# GTY_Transceivers.net
KiCad netlist of a schematic drawn in Altium Designer
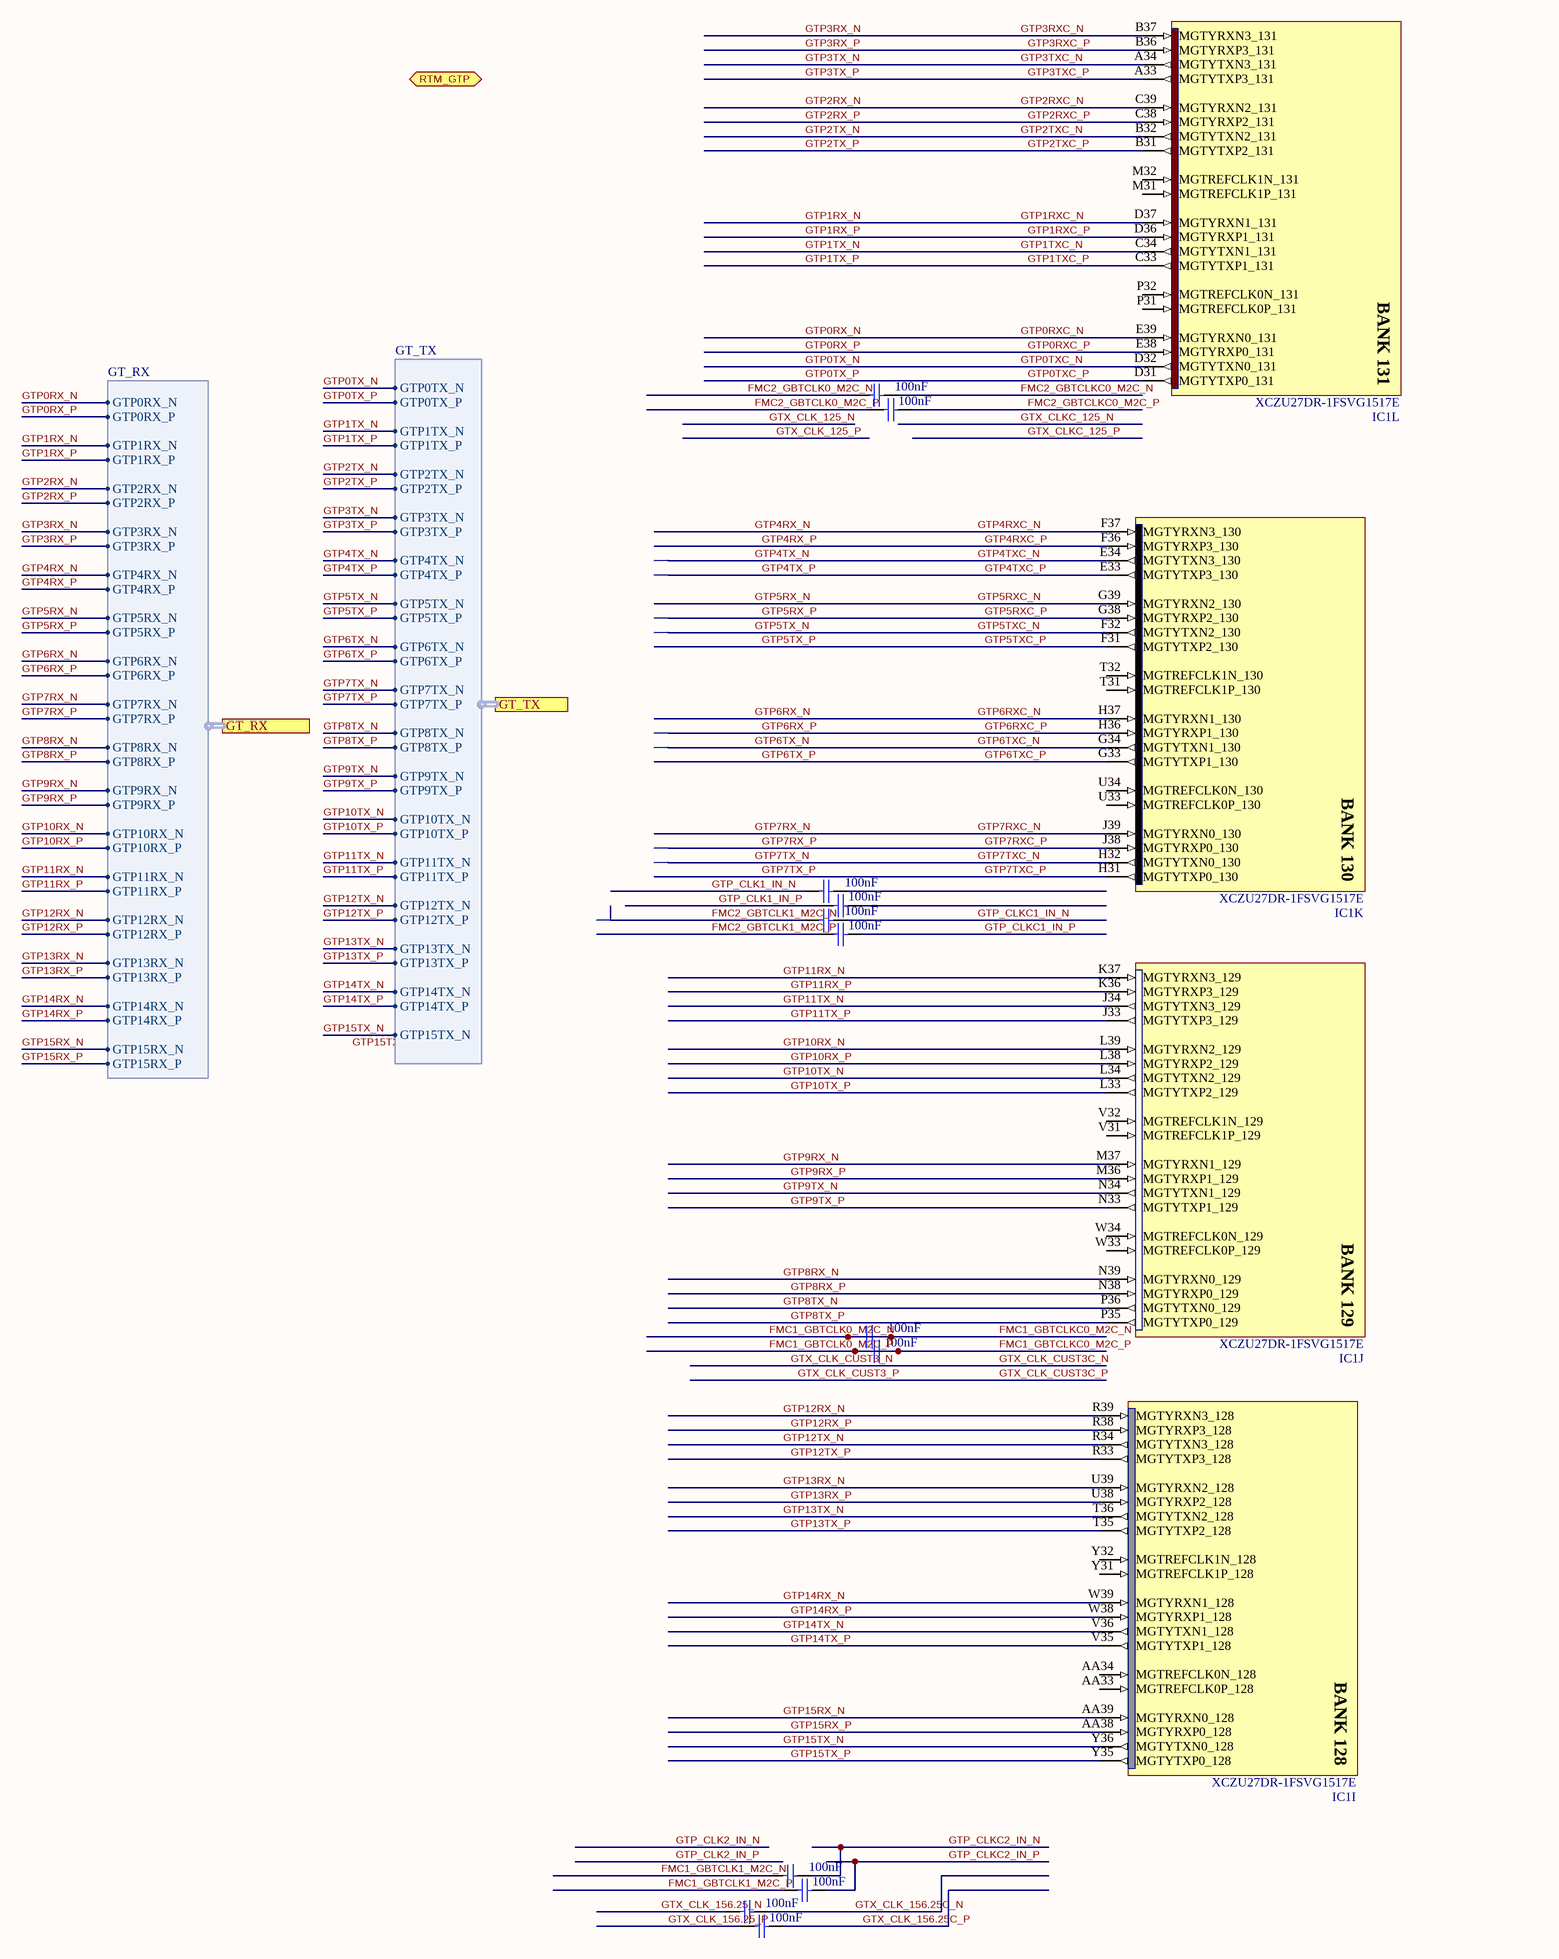
[diagram p0: GTY_Transceivers.SchDoc]

(export (version "E")
  (design (tool "Eeschema 10.0.6"))
  (components
    (comp (ref "C435")
      (value "100nF")
      (fields
        (field (name "$$NOTCOMMONPROPERTY_GENERAL PART NUMBER") "CC0201_100NF_6.3V_10%_X5R")
        (field (name "$$NOTCOMMONPROPERTY_MANUFACTURER1 PART NUMBER") "02016D104KAT2A")
        (field (name "MANUFACTURER") "GENERIC")
      )
      (libsource (lib "altium-import") (part "root_0__*"))
    )
    (comp (ref "C436")
      (value "100nF")
      (fields
        (field (name "$$NOTCOMMONPROPERTY_GENERAL PART NUMBER") "CC0201_100NF_6.3V_10%_X5R")
        (field (name "$$NOTCOMMONPROPERTY_MANUFACTURER1 PART NUMBER") "02016D104KAT2A")
        (field (name "MANUFACTURER") "GENERIC")
      )
      (libsource (lib "altium-import") (part "root_0__*"))
    )
    (comp (ref "C595")
      (value "100nF")
      (fields
        (field (name "$$NOTCOMMONPROPERTY_GENERAL PART NUMBER") "CC0201_100NF_6.3V_10%_X5R")
        (field (name "$$NOTCOMMONPROPERTY_MANUFACTURER1 PART NUMBER") "02016D104KAT2A")
        (field (name "MANUFACTURER") "GENERIC")
      )
      (libsource (lib "altium-import") (part "root_0__*"))
    )
    (comp (ref "C596")
      (value "100nF")
      (fields
        (field (name "$$NOTCOMMONPROPERTY_GENERAL PART NUMBER") "CC0201_100NF_6.3V_10%_X5R")
        (field (name "$$NOTCOMMONPROPERTY_MANUFACTURER1 PART NUMBER") "02016D104KAT2A")
        (field (name "MANUFACTURER") "GENERIC")
      )
      (libsource (lib "altium-import") (part "root_0__*"))
    )
    (comp (ref "C623")
      (value "100nF")
      (fields
        (field (name "$$NOTCOMMONPROPERTY_GENERAL PART NUMBER") "CC0201_100NF_6.3V_10%_X5R")
        (field (name "$$NOTCOMMONPROPERTY_MANUFACTURER1 PART NUMBER") "02016D104KAT2A")
        (field (name "MANUFACTURER") "GENERIC")
      )
      (libsource (lib "altium-import") (part "root_0__*"))
    )
    (comp (ref "C624")
      (value "100nF")
      (fields
        (field (name "$$NOTCOMMONPROPERTY_GENERAL PART NUMBER") "CC0201_100NF_6.3V_10%_X5R")
        (field (name "$$NOTCOMMONPROPERTY_MANUFACTURER1 PART NUMBER") "02016D104KAT2A")
        (field (name "MANUFACTURER") "GENERIC")
      )
      (libsource (lib "altium-import") (part "root_0__*"))
    )
    (comp (ref "C625")
      (value "100nF")
      (fields
        (field (name "$$NOTCOMMONPROPERTY_GENERAL PART NUMBER") "CC0201_100NF_6.3V_10%_X5R")
        (field (name "$$NOTCOMMONPROPERTY_MANUFACTURER1 PART NUMBER") "02016D104KAT2A")
        (field (name "MANUFACTURER") "GENERIC")
      )
      (libsource (lib "altium-import") (part "root_0__*"))
    )
    (comp (ref "C626")
      (value "100nF")
      (fields
        (field (name "$$NOTCOMMONPROPERTY_GENERAL PART NUMBER") "CC0201_100NF_6.3V_10%_X5R")
        (field (name "$$NOTCOMMONPROPERTY_MANUFACTURER1 PART NUMBER") "02016D104KAT2A")
        (field (name "MANUFACTURER") "GENERIC")
      )
      (libsource (lib "altium-import") (part "root_0__*"))
    )
    (comp (ref "C643")
      (value "100nF")
      (fields
        (field (name "$$NOTCOMMONPROPERTY_GENERAL PART NUMBER") "CC0201_100NF_6.3V_10%_X5R")
        (field (name "$$NOTCOMMONPROPERTY_MANUFACTURER1 PART NUMBER") "02016D104KAT2A")
        (field (name "MANUFACTURER") "GENERIC")
      )
      (libsource (lib "altium-import") (part "root_0__*"))
    )
    (comp (ref "C644")
      (value "100nF")
      (fields
        (field (name "$$NOTCOMMONPROPERTY_GENERAL PART NUMBER") "CC0201_100NF_6.3V_10%_X5R")
        (field (name "$$NOTCOMMONPROPERTY_MANUFACTURER1 PART NUMBER") "02016D104KAT2A")
        (field (name "MANUFACTURER") "GENERIC")
      )
      (libsource (lib "altium-import") (part "root_0__*"))
    )
    (comp (ref "C665")
      (value "100nF")
      (fields
        (field (name "$$NOTCOMMONPROPERTY_GENERAL PART NUMBER") "CC0201_100NF_6.3V_10%_X5R")
        (field (name "$$NOTCOMMONPROPERTY_MANUFACTURER1 PART NUMBER") "02016D104KAT2A")
        (field (name "MANUFACTURER") "GENERIC")
      )
      (libsource (lib "altium-import") (part "root_0__*"))
    )
    (comp (ref "C666")
      (value "100nF")
      (fields
        (field (name "$$NOTCOMMONPROPERTY_GENERAL PART NUMBER") "CC0201_100NF_6.3V_10%_X5R")
        (field (name "$$NOTCOMMONPROPERTY_MANUFACTURER1 PART NUMBER") "02016D104KAT2A")
        (field (name "MANUFACTURER") "GENERIC")
      )
      (libsource (lib "altium-import") (part "root_0__*"))
    )
    (comp (ref "IC1")
      (value "XCZU27DR-1FSVG1517E")
      (footprint "XILINX_FSVG1517 (XCZU27DR)")
      (fields (field (name "MANUFACTURER") "XILINX") (field (name "AUTHOR") "CERN DEM MR"))
      (libsource (lib "ICs And Semiconductors") (part "XCZU27DR-1FSVG1517E"))
    )
  )
  (nets
    (net (code "3") (name "/FMC1_GBTCLK0_M2C_N") (class "Default")
      (node (ref "C643") (pin "1") (pinfunction "1_1") (pintype "passive"))
      (node (ref "C643") (pin "2") (pinfunction "2_2") (pintype "passive"))
    )
    (net (code "4") (name "/FMC1_GBTCLK0_M2C_P") (class "Default")
      (node (ref "C644") (pin "1") (pinfunction "1_1") (pintype "passive"))
      (node (ref "C644") (pin "2") (pinfunction "2_2") (pintype "passive"))
    )
    (net (code "5") (name "/FMC1_GBTCLK1_M2C_N") (class "Default")
      (node (ref "C665") (pin "1") (pinfunction "1_1") (pintype "passive"))
    )
    (net (code "6") (name "/FMC1_GBTCLK1_M2C_P") (class "Default")
      (node (ref "C666") (pin "1") (pinfunction "1_1") (pintype "passive"))
    )
    (net (code "7") (name "/FMC2_GBTCLK0_M2C_N") (class "Default")
      (node (ref "C595") (pin "1") (pinfunction "1_1") (pintype "passive"))
    )
    (net (code "8") (name "/FMC2_GBTCLK0_M2C_P") (class "Default")
      (node (ref "C596") (pin "1") (pinfunction "1_1") (pintype "passive"))
    )
    (net (code "9") (name "/FMC2_GBTCLK1_M2C_N") (class "Default")
      (node (ref "C625") (pin "1") (pinfunction "1_1") (pintype "passive"))
    )
    (net (code "10") (name "/FMC2_GBTCLK1_M2C_P") (class "Default")
      (node (ref "C626") (pin "1") (pinfunction "1_1") (pintype "passive"))
    )
    (net (code "11") (name "/FMC2_GBTCLKC0_M2C_N") (class "Default")
      (node (ref "C595") (pin "2") (pinfunction "2_2") (pintype "passive"))
    )
    (net (code "12") (name "/FMC2_GBTCLKC0_M2C_P") (class "Default")
      (node (ref "C596") (pin "2") (pinfunction "2_2") (pintype "passive"))
    )
    (net (code "13") (name "/GTP0RXC_N") (class "Default")
      (node (ref "IC1") (pin "E39") (pinfunction "MGTYRXN0_131_E39") (pintype "input"))
    )
    (net (code "14") (name "/GTP0RXC_P") (class "Default")
      (node (ref "IC1") (pin "E38") (pinfunction "MGTYRXP0_131_E38") (pintype "input"))
    )
    (net (code "15") (name "/GTP0TXC_N") (class "Default")
      (node (ref "IC1") (pin "D32") (pinfunction "MGTYTXN0_131_D32") (pintype "output"))
    )
    (net (code "16") (name "/GTP0TXC_P") (class "Default")
      (node (ref "IC1") (pin "D31") (pinfunction "MGTYTXP0_131_D31") (pintype "output"))
    )
    (net (code "17") (name "/GTP1RXC_N") (class "Default")
      (node (ref "IC1") (pin "D37") (pinfunction "MGTYRXN1_131_D37") (pintype "input"))
    )
    (net (code "18") (name "/GTP1RXC_P") (class "Default")
      (node (ref "IC1") (pin "D36") (pinfunction "MGTYRXP1_131_D36") (pintype "input"))
    )
    (net (code "19") (name "/GTP1TXC_N") (class "Default")
      (node (ref "IC1") (pin "C34") (pinfunction "MGTYTXN1_131_C34") (pintype "output"))
    )
    (net (code "20") (name "/GTP1TXC_P") (class "Default")
      (node (ref "IC1") (pin "C33") (pinfunction "MGTYTXP1_131_C33") (pintype "output"))
    )
    (net (code "21") (name "/GTP2RXC_N") (class "Default")
      (node (ref "IC1") (pin "C39") (pinfunction "MGTYRXN2_131_C39") (pintype "input"))
    )
    (net (code "22") (name "/GTP2RXC_P") (class "Default")
      (node (ref "IC1") (pin "C38") (pinfunction "MGTYRXP2_131_C38") (pintype "input"))
    )
    (net (code "23") (name "/GTP2TXC_N") (class "Default")
      (node (ref "IC1") (pin "B32") (pinfunction "MGTYTXN2_131_B32") (pintype "output"))
    )
    (net (code "24") (name "/GTP2TXC_P") (class "Default")
      (node (ref "IC1") (pin "B31") (pinfunction "MGTYTXP2_131_B31") (pintype "output"))
    )
    (net (code "25") (name "/GTP3RXC_N") (class "Default")
      (node (ref "IC1") (pin "B37") (pinfunction "MGTYRXN3_131_B37") (pintype "input"))
    )
    (net (code "26") (name "/GTP3RXC_P") (class "Default")
      (node (ref "IC1") (pin "B36") (pinfunction "MGTYRXP3_131_B36") (pintype "input"))
    )
    (net (code "27") (name "/GTP3TXC_N") (class "Default")
      (node (ref "IC1") (pin "A34") (pinfunction "MGTYTXN3_131_A34") (pintype "output"))
    )
    (net (code "28") (name "/GTP3TXC_P") (class "Default")
      (node (ref "IC1") (pin "A33") (pinfunction "MGTYTXP3_131_A33") (pintype "output"))
    )
    (net (code "29") (name "/GTP4RXC_N") (class "Default")
      (node (ref "IC1") (pin "F37") (pinfunction "MGTYRXN3_130_F37") (pintype "input"))
    )
    (net (code "30") (name "/GTP4RXC_P") (class "Default")
      (node (ref "IC1") (pin "F36") (pinfunction "MGTYRXP3_130_F36") (pintype "input"))
    )
    (net (code "31") (name "/GTP4TXC_N") (class "Default")
      (node (ref "IC1") (pin "E34") (pinfunction "MGTYTXN3_130_E34") (pintype "output"))
    )
    (net (code "32") (name "/GTP4TXC_P") (class "Default")
      (node (ref "IC1") (pin "E33") (pinfunction "MGTYTXP3_130_E33") (pintype "output"))
    )
    (net (code "33") (name "/GTP5RXC_N") (class "Default")
      (node (ref "IC1") (pin "G39") (pinfunction "MGTYRXN2_130_G39") (pintype "input"))
    )
    (net (code "34") (name "/GTP5RXC_P") (class "Default")
      (node (ref "IC1") (pin "G38") (pinfunction "MGTYRXP2_130_G38") (pintype "input"))
    )
    (net (code "35") (name "/GTP5TXC_N") (class "Default")
      (node (ref "IC1") (pin "F32") (pinfunction "MGTYTXN2_130_F32") (pintype "output"))
    )
    (net (code "36") (name "/GTP5TXC_P") (class "Default")
      (node (ref "IC1") (pin "F31") (pinfunction "MGTYTXP2_130_F31") (pintype "output"))
    )
    (net (code "37") (name "/GTP6RXC_N") (class "Default")
      (node (ref "IC1") (pin "H37") (pinfunction "MGTYRXN1_130_H37") (pintype "input"))
    )
    (net (code "38") (name "/GTP6RXC_P") (class "Default")
      (node (ref "IC1") (pin "H36") (pinfunction "MGTYRXP1_130_H36") (pintype "input"))
    )
    (net (code "39") (name "/GTP6TXC_N") (class "Default")
      (node (ref "IC1") (pin "G34") (pinfunction "MGTYTXN1_130_G34") (pintype "output"))
    )
    (net (code "40") (name "/GTP6TXC_P") (class "Default")
      (node (ref "IC1") (pin "G33") (pinfunction "MGTYTXP1_130_G33") (pintype "output"))
    )
    (net (code "41") (name "/GTP7RXC_N") (class "Default")
      (node (ref "IC1") (pin "J39") (pinfunction "MGTYRXN0_130_J39") (pintype "input"))
    )
    (net (code "42") (name "/GTP7RXC_P") (class "Default")
      (node (ref "IC1") (pin "J38") (pinfunction "MGTYRXP0_130_J38") (pintype "input"))
    )
    (net (code "43") (name "/GTP7TXC_N") (class "Default")
      (node (ref "IC1") (pin "H32") (pinfunction "MGTYTXN0_130_H32") (pintype "output"))
    )
    (net (code "44") (name "/GTP7TXC_P") (class "Default")
      (node (ref "IC1") (pin "H31") (pinfunction "MGTYTXP0_130_H31") (pintype "output"))
    )
    (net (code "45") (name "/GTP8RX_N") (class "Default")
      (node (ref "IC1") (pin "N39") (pinfunction "MGTYRXN0_129_N39") (pintype "input"))
    )
    (net (code "46") (name "/GTP8RX_P") (class "Default")
      (node (ref "IC1") (pin "N38") (pinfunction "MGTYRXP0_129_N38") (pintype "input"))
    )
    (net (code "47") (name "/GTP8TX_N") (class "Default")
      (node (ref "IC1") (pin "P36") (pinfunction "MGTYTXN0_129_P36") (pintype "output"))
    )
    (net (code "48") (name "/GTP8TX_P") (class "Default")
      (node (ref "IC1") (pin "P35") (pinfunction "MGTYTXP0_129_P35") (pintype "output"))
    )
    (net (code "49") (name "/GTP9RX_N") (class "Default")
      (node (ref "IC1") (pin "M37") (pinfunction "MGTYRXN1_129_M37") (pintype "input"))
    )
    (net (code "50") (name "/GTP9RX_P") (class "Default")
      (node (ref "IC1") (pin "M36") (pinfunction "MGTYRXP1_129_M36") (pintype "input"))
    )
    (net (code "51") (name "/GTP9TX_N") (class "Default")
      (node (ref "IC1") (pin "N34") (pinfunction "MGTYTXN1_129_N34") (pintype "output"))
    )
    (net (code "52") (name "/GTP9TX_P") (class "Default")
      (node (ref "IC1") (pin "N33") (pinfunction "MGTYTXP1_129_N33") (pintype "output"))
    )
    (net (code "53") (name "/GTP10RX_N") (class "Default")
      (node (ref "IC1") (pin "L39") (pinfunction "MGTYRXN2_129_L39") (pintype "input"))
    )
    (net (code "54") (name "/GTP10RX_P") (class "Default")
      (node (ref "IC1") (pin "L38") (pinfunction "MGTYRXP2_129_L38") (pintype "input"))
    )
    (net (code "55") (name "/GTP10TX_N") (class "Default")
      (node (ref "IC1") (pin "L34") (pinfunction "MGTYTXN2_129_L34") (pintype "output"))
    )
    (net (code "56") (name "/GTP10TX_P") (class "Default")
      (node (ref "IC1") (pin "L33") (pinfunction "MGTYTXP2_129_L33") (pintype "output"))
    )
    (net (code "57") (name "/GTP11RX_N") (class "Default")
      (node (ref "IC1") (pin "K37") (pinfunction "MGTYRXN3_129_K37") (pintype "input"))
    )
    (net (code "58") (name "/GTP11RX_P") (class "Default")
      (node (ref "IC1") (pin "K36") (pinfunction "MGTYRXP3_129_K36") (pintype "input"))
    )
    (net (code "59") (name "/GTP11TX_N") (class "Default")
      (node (ref "IC1") (pin "J34") (pinfunction "MGTYTXN3_129_J34") (pintype "output"))
    )
    (net (code "60") (name "/GTP11TX_P") (class "Default")
      (node (ref "IC1") (pin "J33") (pinfunction "MGTYTXP3_129_J33") (pintype "output"))
    )
    (net (code "61") (name "/GTP12RX_N") (class "Default")
      (node (ref "IC1") (pin "R39") (pinfunction "MGTYRXN3_128_R39") (pintype "input"))
    )
    (net (code "62") (name "/GTP12RX_P") (class "Default")
      (node (ref "IC1") (pin "R38") (pinfunction "MGTYRXP3_128_R38") (pintype "input"))
    )
    (net (code "63") (name "/GTP12TX_N") (class "Default")
      (node (ref "IC1") (pin "R34") (pinfunction "MGTYTXN3_128_R34") (pintype "output"))
    )
    (net (code "64") (name "/GTP12TX_P") (class "Default")
      (node (ref "IC1") (pin "R33") (pinfunction "MGTYTXP3_128_R33") (pintype "output"))
    )
    (net (code "65") (name "/GTP13RX_N") (class "Default")
      (node (ref "IC1") (pin "U39") (pinfunction "MGTYRXN2_128_U39") (pintype "input"))
    )
    (net (code "66") (name "/GTP13RX_P") (class "Default")
      (node (ref "IC1") (pin "U38") (pinfunction "MGTYRXP2_128_U38") (pintype "input"))
    )
    (net (code "67") (name "/GTP13TX_N") (class "Default")
      (node (ref "IC1") (pin "T36") (pinfunction "MGTYTXN2_128_T36") (pintype "output"))
    )
    (net (code "68") (name "/GTP13TX_P") (class "Default")
      (node (ref "IC1") (pin "T35") (pinfunction "MGTYTXP2_128_T35") (pintype "output"))
    )
    (net (code "69") (name "/GTP14RX_N") (class "Default")
      (node (ref "IC1") (pin "W39") (pinfunction "MGTYRXN1_128_W39") (pintype "input"))
    )
    (net (code "70") (name "/GTP14RX_P") (class "Default")
      (node (ref "IC1") (pin "W38") (pinfunction "MGTYRXP1_128_W38") (pintype "input"))
    )
    (net (code "71") (name "/GTP14TX_N") (class "Default")
      (node (ref "IC1") (pin "V36") (pinfunction "MGTYTXN1_128_V36") (pintype "output"))
    )
    (net (code "72") (name "/GTP14TX_P") (class "Default")
      (node (ref "IC1") (pin "V35") (pinfunction "MGTYTXP1_128_V35") (pintype "output"))
    )
    (net (code "73") (name "/GTP15RX_N") (class "Default")
      (node (ref "IC1") (pin "AA39") (pinfunction "MGTYRXN0_128_AA39") (pintype "input"))
    )
    (net (code "74") (name "/GTP15RX_P") (class "Default")
      (node (ref "IC1") (pin "AA38") (pinfunction "MGTYRXP0_128_AA38") (pintype "input"))
    )
    (net (code "75") (name "/GTP15TX_N") (class "Default")
      (node (ref "IC1") (pin "Y36") (pinfunction "MGTYTXN0_128_Y36") (pintype "output"))
    )
    (net (code "76") (name "/GTP15TX_P") (class "Default")
      (node (ref "IC1") (pin "Y35") (pinfunction "MGTYTXP0_128_Y35") (pintype "output"))
    )
    (net (code "77") (name "/GTP_CLK1_IN_N") (class "Default")
      (node (ref "C623") (pin "1") (pinfunction "1_1") (pintype "passive"))
    )
    (net (code "78") (name "/GTP_CLK1_IN_P") (class "Default")
      (node (ref "C624") (pin "1") (pinfunction "1_1") (pintype "passive"))
    )
    (net (code "81") (name "/GTP_CLKC1_IN_N") (class "Default")
      (node (ref "C625") (pin "2") (pinfunction "2_2") (pintype "passive"))
    )
    (net (code "82") (name "/GTP_CLKC1_IN_P") (class "Default")
      (node (ref "C626") (pin "2") (pinfunction "2_2") (pintype "passive"))
    )
    (net (code "83") (name "/GTP_CLKC2_IN_N") (class "Default")
      (node (ref "C665") (pin "2") (pinfunction "2_2") (pintype "passive"))
    )
    (net (code "84") (name "/GTP_CLKC2_IN_P") (class "Default")
      (node (ref "C666") (pin "2") (pinfunction "2_2") (pintype "passive"))
    )
    (net (code "89") (name "/GTX_CLK_156.25C_N") (class "Default")
      (node (ref "C435") (pin "2") (pinfunction "2_2") (pintype "passive"))
    )
    (net (code "90") (name "/GTX_CLK_156.25C_P") (class "Default")
      (node (ref "C436") (pin "2") (pinfunction "2_2") (pintype "passive"))
    )
    (net (code "91") (name "/GTX_CLK_156.25_N") (class "Default")
      (node (ref "C435") (pin "1") (pinfunction "1_1") (pintype "passive"))
    )
    (net (code "92") (name "/GTX_CLK_156.25_P") (class "Default")
      (node (ref "C436") (pin "1") (pinfunction "1_1") (pintype "passive"))
    )
    (net (code "98") (name "unconnected-(C623-Pad2)") (class "Default")
      (node (ref "C623") (pin "2") (pinfunction "2_2") (pintype "passive"))
    )
    (net (code "99") (name "unconnected-(C624-Pad2)") (class "Default")
      (node (ref "C624") (pin "2") (pinfunction "2_2") (pintype "passive"))
    )
    (net (code "100") (name "unconnected-(IC1I-MGTREFCLK0N_128-PadAA34)") (class "Default")
      (node (ref "IC1") (pin "AA34") (pinfunction "MGTREFCLK0N_128_AA34") (pintype "input"))
    )
    (net (code "101") (name "unconnected-(IC1I-MGTREFCLK0P_128-PadAA33)") (class "Default")
      (node (ref "IC1") (pin "AA33") (pinfunction "MGTREFCLK0P_128_AA33") (pintype "input"))
    )
    (net (code "102") (name "unconnected-(IC1I-MGTREFCLK1N_128-PadY32)") (class "Default")
      (node (ref "IC1") (pin "Y32") (pinfunction "MGTREFCLK1N_128_Y32") (pintype "input"))
    )
    (net (code "103") (name "unconnected-(IC1I-MGTREFCLK1P_128-PadY31)") (class "Default")
      (node (ref "IC1") (pin "Y31") (pinfunction "MGTREFCLK1P_128_Y31") (pintype "input"))
    )
    (net (code "104") (name "unconnected-(IC1J-MGTREFCLK0N_129-PadW34)") (class "Default")
      (node (ref "IC1") (pin "W34") (pinfunction "MGTREFCLK0N_129_W34") (pintype "input"))
    )
    (net (code "105") (name "unconnected-(IC1J-MGTREFCLK0P_129-PadW33)") (class "Default")
      (node (ref "IC1") (pin "W33") (pinfunction "MGTREFCLK0P_129_W33") (pintype "input"))
    )
    (net (code "106") (name "unconnected-(IC1J-MGTREFCLK1N_129-PadV32)") (class "Default")
      (node (ref "IC1") (pin "V32") (pinfunction "MGTREFCLK1N_129_V32") (pintype "input"))
    )
    (net (code "107") (name "unconnected-(IC1J-MGTREFCLK1P_129-PadV31)") (class "Default")
      (node (ref "IC1") (pin "V31") (pinfunction "MGTREFCLK1P_129_V31") (pintype "input"))
    )
    (net (code "108") (name "unconnected-(IC1K-MGTREFCLK0N_130-PadU34)") (class "Default")
      (node (ref "IC1") (pin "U34") (pinfunction "MGTREFCLK0N_130_U34") (pintype "input"))
    )
    (net (code "109") (name "unconnected-(IC1K-MGTREFCLK0P_130-PadU33)") (class "Default")
      (node (ref "IC1") (pin "U33") (pinfunction "MGTREFCLK0P_130_U33") (pintype "input"))
    )
    (net (code "110") (name "unconnected-(IC1K-MGTREFCLK1N_130-PadT32)") (class "Default")
      (node (ref "IC1") (pin "T32") (pinfunction "MGTREFCLK1N_130_T32") (pintype "input"))
    )
    (net (code "111") (name "unconnected-(IC1K-MGTREFCLK1P_130-PadT31)") (class "Default")
      (node (ref "IC1") (pin "T31") (pinfunction "MGTREFCLK1P_130_T31") (pintype "input"))
    )
    (net (code "112") (name "unconnected-(IC1L-MGTREFCLK0N_131-PadP32)") (class "Default")
      (node (ref "IC1") (pin "P32") (pinfunction "MGTREFCLK0N_131_P32") (pintype "input"))
    )
    (net (code "113") (name "unconnected-(IC1L-MGTREFCLK0P_131-PadP31)") (class "Default")
      (node (ref "IC1") (pin "P31") (pinfunction "MGTREFCLK0P_131_P31") (pintype "input"))
    )
    (net (code "114") (name "unconnected-(IC1L-MGTREFCLK1N_131-PadM32)") (class "Default")
      (node (ref "IC1") (pin "M32") (pinfunction "MGTREFCLK1N_131_M32") (pintype "input"))
    )
    (net (code "115") (name "unconnected-(IC1L-MGTREFCLK1P_131-PadM31)") (class "Default")
      (node (ref "IC1") (pin "M31") (pinfunction "MGTREFCLK1P_131_M31") (pintype "input"))
    )
  )
)
